# Control.net
KiCad netlist of a schematic drawn in Altium Designer
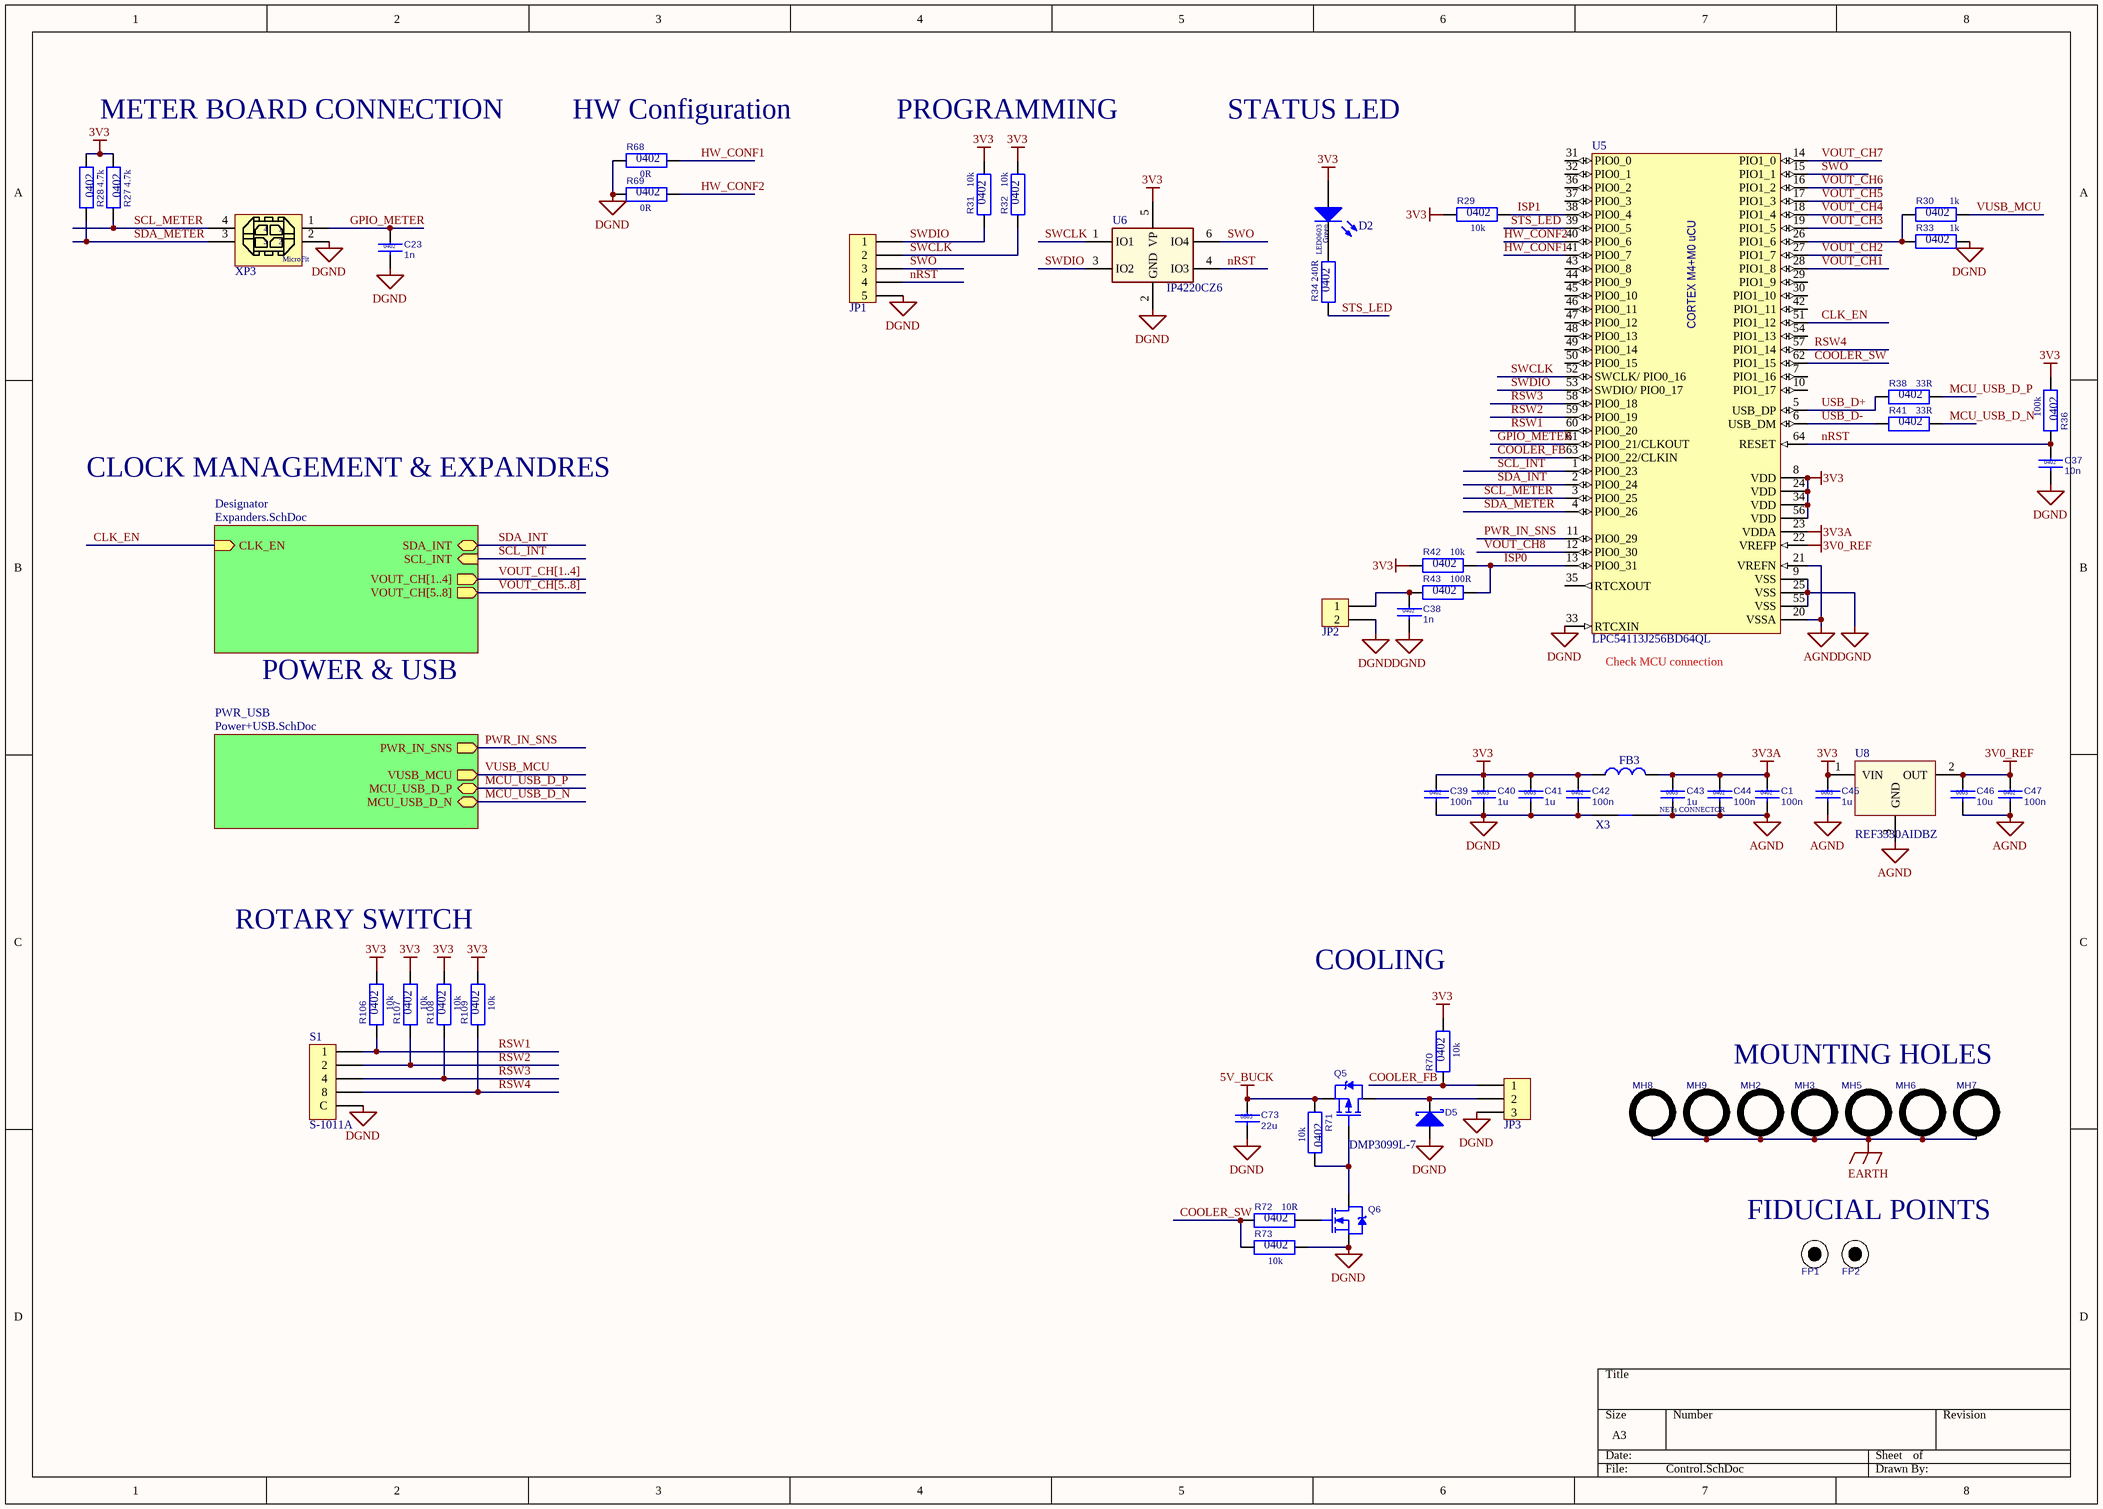
[diagram p0: Control.SchDoc]

(export (version "E")
  (design (tool "Eeschema 10.0.6"))
  (components
    (comp (ref "C1")
      (value "100n")
      (footprint "CC0402M")
      (description "Chip ceramic capacitor")
      (fields
        (field (name "CASE") "0402")
        (field (name "PARTNUMBER") "CC0402K-X7R-25V-100N-M")
        (field (name "MANUFACTURER") "Murata")
        (field (name "PUBLISHER") "alexey.savchenko")
      )
      (libsource (lib "AltiumLib") (part "Capacitor_nonpolar"))
    )
    (comp (ref "C23")
      (value "1n")
      (footprint "CC0402M")
      (description "Chip ceramic capacitor")
      (fields
        (field (name "CASE") "0402")
        (field (name "PARTNUMBER") "CC0402K-X7R-50V-1N-M")
        (field (name "MANUFACTURER") "Yageo")
        (field (name "PUBLISHER") "alexey.savchenko")
      )
      (libsource (lib "AltiumLib") (part "Capacitor_nonpolar"))
    )
    (comp (ref "C37")
      (value "10n")
      (footprint "CC0402M")
      (description "Chip ceramic capacitor")
      (fields
        (field (name "CASE") "0402")
        (field (name "PARTNUMBER") "CC0402K-X7R-50V-10N-M")
        (field (name "MANUFACTURER") "Yageo")
        (field (name "PUBLISHER") "alexey.savchenko")
      )
      (libsource (lib "AltiumLib") (part "Capacitor_nonpolar"))
    )
    (comp (ref "C38")
      (value "1n")
      (footprint "CC0402M")
      (description "Chip ceramic capacitor")
      (fields
        (field (name "CASE") "0402")
        (field (name "PARTNUMBER") "CC0402K-X7R-50V-1N-M")
        (field (name "MANUFACTURER") "Yageo")
        (field (name "PUBLISHER") "alexey.savchenko")
      )
      (libsource (lib "AltiumLib") (part "Capacitor_nonpolar"))
    )
    (comp (ref "C39")
      (value "100n")
      (footprint "CC0402M")
      (description "Chip ceramic capacitor")
      (fields
        (field (name "CASE") "0402")
        (field (name "PARTNUMBER") "CC0402K-X7R-25V-100N-M")
        (field (name "MANUFACTURER") "Murata")
        (field (name "PUBLISHER") "alexey.savchenko")
      )
      (libsource (lib "AltiumLib") (part "Capacitor_nonpolar"))
    )
    (comp (ref "C40")
      (value "1u")
      (footprint "CC0603M")
      (description "Chip ceramic capacitor")
      (fields
        (field (name "CASE") "0603")
        (field (name "PARTNUMBER") "CC0603K-X7R-10V-1U-M")
        (field (name "MANUFACTURER") "Samsung")
        (field (name "PUBLISHER") "alexey.savchenko")
      )
      (libsource (lib "AltiumLib") (part "Capacitor_nonpolar"))
    )
    (comp (ref "C41")
      (value "1u")
      (footprint "CC0603M")
      (description "Chip ceramic capacitor")
      (fields
        (field (name "CASE") "0603")
        (field (name "PARTNUMBER") "CC0603K-X7R-10V-1U-M")
        (field (name "MANUFACTURER") "Samsung")
        (field (name "PUBLISHER") "alexey.savchenko")
      )
      (libsource (lib "AltiumLib") (part "Capacitor_nonpolar"))
    )
    (comp (ref "C42")
      (value "100n")
      (footprint "CC0402M")
      (description "Chip ceramic capacitor")
      (fields
        (field (name "CASE") "0402")
        (field (name "PARTNUMBER") "CC0402K-X7R-25V-100N-M")
        (field (name "MANUFACTURER") "Murata")
        (field (name "PUBLISHER") "alexey.savchenko")
      )
      (libsource (lib "AltiumLib") (part "Capacitor_nonpolar"))
    )
    (comp (ref "C43")
      (value "1u")
      (footprint "CC0603M")
      (description "Chip ceramic capacitor")
      (fields
        (field (name "CASE") "0603")
        (field (name "PARTNUMBER") "CC0603K-X7R-10V-1U-M")
        (field (name "MANUFACTURER") "Samsung")
        (field (name "PUBLISHER") "alexey.savchenko")
      )
      (libsource (lib "AltiumLib") (part "Capacitor_nonpolar"))
    )
    (comp (ref "C44")
      (value "100n")
      (footprint "CC0402M")
      (description "Chip ceramic capacitor")
      (fields
        (field (name "CASE") "0402")
        (field (name "PARTNUMBER") "CC0402K-X7R-25V-100N-M")
        (field (name "MANUFACTURER") "Murata")
        (field (name "PUBLISHER") "alexey.savchenko")
      )
      (libsource (lib "AltiumLib") (part "Capacitor_nonpolar"))
    )
    (comp (ref "C45")
      (value "1u")
      (footprint "CC0603M")
      (description "Chip ceramic capacitor")
      (fields
        (field (name "CASE") "0603")
        (field (name "PARTNUMBER") "CC0603K-X7R-10V-1U-M")
        (field (name "MANUFACTURER") "Samsung")
        (field (name "PUBLISHER") "alexey.savchenko")
      )
      (libsource (lib "AltiumLib") (part "Capacitor_nonpolar"))
    )
    (comp (ref "C46")
      (value "10u")
      (footprint "CC0603M")
      (description "Chip ceramic capacitor")
      (fields
        (field (name "CASE") "0603")
        (field (name "PARTNUMBER") "CC0603K-X5R-10V-10U-M")
        (field (name "MANUFACTURER") "Murata")
        (field (name "PUBLISHER") "alexey.savchenko")
      )
      (libsource (lib "AltiumLib") (part "Capacitor_nonpolar"))
    )
    (comp (ref "C47")
      (value "100n")
      (footprint "CC0402M")
      (description "Chip ceramic capacitor")
      (fields
        (field (name "CASE") "0402")
        (field (name "PARTNUMBER") "CC0402K-X7R-25V-100N-M")
        (field (name "MANUFACTURER") "Murata")
        (field (name "PUBLISHER") "alexey.savchenko")
      )
      (libsource (lib "AltiumLib") (part "Capacitor_nonpolar"))
    )
    (comp (ref "C73")
      (value "22u")
      (footprint "CC0805M")
      (description "Chip ceramic capacitor")
      (fields
        (field (name "CASE") "0805")
        (field (name "PARTNUMBER") "CC0805K-X5R-10V-22U-M")
        (field (name "MANUFACTURER") "Samsung")
        (field (name "PUBLISHER") "alexey.savchenko")
      )
      (libsource (lib "AltiumLib") (part "Capacitor_nonpolar"))
    )
    (comp (ref "D2")
      (value "150060GS75000")
      (footprint "LED0603")
      (description "LED GREEN CLEAR 0603 SMD")
      (fields
        (field (name "CASE") "LED0603")
        (field (name "COLOR") "Green")
        (field (name "MANUFACTURER") "Würth Elektronik")
        (field (name "PUBLISHER") "alexey.savchenko")
      )
      (libsource (lib "AltiumLib") (part "LED"))
    )
    (comp (ref "D5")
      (value "BAT54HT1G")
      (footprint "SOD323")
      (description "DIODE SCHOTTKY 30V 200MA SOD323")
      (fields (field (name "MANUFACTURER") "ON Semiconductor") (field (name "PUBLISHER") "alexey.savchenko"))
      (libsource (lib "AltiumLib") (part "SCHOTTKY_DIODE"))
    )
    (comp (ref "FB3")
      (value "BLM18HG102SN1D")
      (footprint "FB0603M")
      (description "FERRITE BEAD 1 KOHM 0603 1LN")
      (fields (field (name "MANUFACTURER") "Murata") (field (name "PUBLISHER") "alexey.savchenko"))
      (libsource (lib "AltiumLib") (part "FerriteBead"))
    )
    (comp (ref "FP1")
      (value "FP")
      (footprint "FP")
      (description "No BOM component to short circuit 2 nets")
      (fields (field (name "MANUFACTURER") "NULL") (field (name "PUBLISHER") "alexey.savchenko"))
      (libsource (lib "AltiumLib") (part "FP"))
    )
    (comp (ref "FP2")
      (value "FP")
      (footprint "FP")
      (description "No BOM component to short circuit 2 nets")
      (fields (field (name "MANUFACTURER") "NULL") (field (name "PUBLISHER") "alexey.savchenko"))
      (libsource (lib "AltiumLib") (part "FP"))
    )
    (comp (ref "JP1")
      (value "HEADER-2.54-THR-1x5-MV")
      (footprint "HEADER-2.54-THR-1x5-MV")
      (description "Header Connector, 2.54mm pitch, Single, 5 contacts, Male, Vertical")
      (fields (field (name "MANUFACTURER") "Adam Tech") (field (name "PUBLISHER") "alexey.savchenko"))
      (libsource (lib "AltiumLib") (part "HEADER-1x5"))
    )
    (comp (ref "JP2")
      (value "HEADER-2.54-THR-1x2-MV")
      (footprint "HEADER-2.54-THR-1x2-MV")
      (description "Header Connector, 2.54mm pitch, Single, 2 contacts, Male, Vertical")
      (fields (field (name "MANUFACTURER") "Adam Tech") (field (name "PUBLISHER") "alexey.savchenko"))
      (libsource (lib "AltiumLib") (part "HEADER-1x2"))
    )
    (comp (ref "JP3")
      (value "HEADER-2.54-THR-1x3-MV")
      (footprint "HEADER-2.54-THR-1x3-MV")
      (description "Header Connector, 2.54mm pitch, Single, 3 contacts, Male, Vertical")
      (fields (field (name "MANUFACTURER") "Adam Tech") (field (name "PUBLISHER") "alexey.savchenko"))
      (libsource (lib "AltiumLib") (part "HEADER-1x3"))
    )
    (comp (ref "MH2")
      (value "MH-3.5-PLATED")
      (footprint "MH_3.5_PLATED")
      (description "Mounting Hole")
      (fields (field (name "MANUFACTURER") "NULL") (field (name "PUBLISHER") "alexey.savchenko"))
      (libsource (lib "AltiumLib") (part "MH_MISC"))
    )
    (comp (ref "MH3")
      (value "MH-3.5-PLATED")
      (footprint "MH_3.5_PLATED")
      (description "Mounting Hole")
      (fields (field (name "MANUFACTURER") "NULL") (field (name "PUBLISHER") "alexey.savchenko"))
      (libsource (lib "AltiumLib") (part "MH_MISC"))
    )
    (comp (ref "MH5")
      (value "MH-3.5-PLATED")
      (footprint "MH_3.5_PLATED")
      (description "Mounting Hole")
      (fields (field (name "MANUFACTURER") "NULL") (field (name "PUBLISHER") "alexey.savchenko"))
      (libsource (lib "AltiumLib") (part "MH_MISC"))
    )
    (comp (ref "MH6")
      (value "MH-3.5-PLATED")
      (footprint "MH_3.5_PLATED")
      (description "Mounting Hole")
      (fields (field (name "MANUFACTURER") "NULL") (field (name "PUBLISHER") "alexey.savchenko"))
      (libsource (lib "AltiumLib") (part "MH_MISC"))
    )
    (comp (ref "MH7")
      (value "MH-3.5-PLATED")
      (footprint "MH_3.5_PLATED")
      (description "Mounting Hole")
      (fields (field (name "MANUFACTURER") "NULL") (field (name "PUBLISHER") "alexey.savchenko"))
      (libsource (lib "AltiumLib") (part "MH_MISC"))
    )
    (comp (ref "MH8")
      (value "MH-3.5-PLATED")
      (footprint "MH_3.5_PLATED")
      (description "Mounting Hole")
      (fields (field (name "MANUFACTURER") "NULL") (field (name "PUBLISHER") "alexey.savchenko"))
      (libsource (lib "AltiumLib") (part "MH_MISC"))
    )
    (comp (ref "MH9")
      (value "MH-3.5-PLATED")
      (footprint "MH_3.5_PLATED")
      (description "Mounting Hole")
      (fields (field (name "MANUFACTURER") "NULL") (field (name "PUBLISHER") "alexey.savchenko"))
      (libsource (lib "AltiumLib") (part "MH_MISC"))
    )
    (comp (ref "Q5")
      (value "DMP3099L-7")
      (footprint "SOT23-3")
      (description "P-Channel 30V 3.8A (Ta) 1.08W (Ta) Surface Mount SOT-23")
      (fields (field (name "MANUFACTURER") "Diodes") (field (name "PUBLISHER") "alexey.savchenko"))
      (libsource (lib "AltiumLib") (part "MOSFET_P-CH"))
    )
    (comp (ref "Q6")
      (value "NX3020NAKW,115")
      (footprint "SOT323")
      (description "MOSFET N-CH 30V 180MA SOT323")
      (fields (field (name "MANUFACTURER") "Nexperia") (field (name "PUBLISHER") "alexey.savchenko"))
      (libsource (lib "AltiumLib") (part "MOSFET_N-CH"))
    )
    (comp (ref "R27")
      (value "4.7k")
      (footprint "RC0402M")
      (description "Chip resistor")
      (fields
        (field (name "CASE") "0402")
        (field (name "PARTNUMBER") "RC0402F-4K7-M")
        (field (name "POWER") "0.063W")
        (field (name "PUBLISHER") "alexey.savchenko")
      )
      (libsource (lib "AltiumLib") (part "Resistor"))
    )
    (comp (ref "R28")
      (value "4.7k")
      (footprint "RC0402M")
      (description "Chip resistor")
      (fields
        (field (name "CASE") "0402")
        (field (name "PARTNUMBER") "RC0402F-4K7-M")
        (field (name "POWER") "0.063W")
        (field (name "PUBLISHER") "alexey.savchenko")
      )
      (libsource (lib "AltiumLib") (part "Resistor"))
    )
    (comp (ref "R29")
      (value "10k")
      (footprint "RC0402M")
      (description "Chip resistor")
      (fields
        (field (name "CASE") "0402")
        (field (name "PARTNUMBER") "RC0402F-10K-M")
        (field (name "POWER") "0.063W")
        (field (name "PUBLISHER") "alexey.savchenko")
      )
      (libsource (lib "AltiumLib") (part "Resistor"))
    )
    (comp (ref "R30")
      (value "1k")
      (footprint "RC0402M")
      (description "Chip resistor")
      (fields
        (field (name "CASE") "0402")
        (field (name "PARTNUMBER") "RC0402F-1K-M")
        (field (name "POWER") "0.063W")
        (field (name "PUBLISHER") "alexey.savchenko")
      )
      (libsource (lib "AltiumLib") (part "Resistor"))
    )
    (comp (ref "R31")
      (value "10k")
      (footprint "RC0402M")
      (description "Chip resistor")
      (fields
        (field (name "CASE") "0402")
        (field (name "PARTNUMBER") "RC0402F-10K-M")
        (field (name "POWER") "0.063W")
        (field (name "PUBLISHER") "alexey.savchenko")
      )
      (libsource (lib "AltiumLib") (part "Resistor"))
    )
    (comp (ref "R32")
      (value "10k")
      (footprint "RC0402M")
      (description "Chip resistor")
      (fields
        (field (name "CASE") "0402")
        (field (name "PARTNUMBER") "RC0402F-10K-M")
        (field (name "POWER") "0.063W")
        (field (name "PUBLISHER") "alexey.savchenko")
      )
      (libsource (lib "AltiumLib") (part "Resistor"))
    )
    (comp (ref "R33")
      (value "1k")
      (footprint "RC0402M")
      (description "Chip resistor")
      (fields
        (field (name "CASE") "0402")
        (field (name "PARTNUMBER") "RC0402F-1K-M")
        (field (name "POWER") "0.063W")
        (field (name "PUBLISHER") "alexey.savchenko")
      )
      (libsource (lib "AltiumLib") (part "Resistor"))
    )
    (comp (ref "R34")
      (value "240R")
      (footprint "RC0402M")
      (description "Chip resistor")
      (fields
        (field (name "CASE") "0402")
        (field (name "PARTNUMBER") "RC0402F-240R-M")
        (field (name "POWER") "0.063W")
        (field (name "PUBLISHER") "alexey.savchenko")
      )
      (libsource (lib "AltiumLib") (part "Resistor"))
    )
    (comp (ref "R36")
      (value "100k")
      (footprint "RC0402M")
      (description "Chip resistor")
      (fields
        (field (name "CASE") "0402")
        (field (name "PARTNUMBER") "RC0402F-100K-M")
        (field (name "POWER") "0.063W")
        (field (name "PUBLISHER") "alexey.savchenko")
      )
      (libsource (lib "AltiumLib") (part "Resistor"))
    )
    (comp (ref "R38")
      (value "33R")
      (footprint "RC0402M")
      (description "Chip resistor")
      (fields
        (field (name "CASE") "0402")
        (field (name "PARTNUMBER") "RC0402F-33R-M")
        (field (name "POWER") "0.063W")
        (field (name "PUBLISHER") "alexey.savchenko")
      )
      (libsource (lib "AltiumLib") (part "Resistor"))
    )
    (comp (ref "R41")
      (value "33R")
      (footprint "RC0402M")
      (description "Chip resistor")
      (fields
        (field (name "CASE") "0402")
        (field (name "PARTNUMBER") "RC0402F-33R-M")
        (field (name "POWER") "0.063W")
        (field (name "PUBLISHER") "alexey.savchenko")
      )
      (libsource (lib "AltiumLib") (part "Resistor"))
    )
    (comp (ref "R42")
      (value "10k")
      (footprint "RC0402M")
      (description "Chip resistor")
      (fields
        (field (name "CASE") "0402")
        (field (name "PARTNUMBER") "RC0402F-10K-M")
        (field (name "POWER") "0.063W")
        (field (name "PUBLISHER") "alexey.savchenko")
      )
      (libsource (lib "AltiumLib") (part "Resistor"))
    )
    (comp (ref "R43")
      (value "100R")
      (footprint "RC0402M")
      (description "Chip resistor")
      (fields
        (field (name "CASE") "0402")
        (field (name "PARTNUMBER") "RC0402F-100R-M")
        (field (name "POWER") "0.063W")
        (field (name "PUBLISHER") "alexey.savchenko")
      )
      (libsource (lib "AltiumLib") (part "Resistor"))
    )
    (comp (ref "R68")
      (value "0R")
      (footprint "RC0402M")
      (description "Chip resistor")
      (fields
        (field (name "CASE") "0402")
        (field (name "PARTNUMBER") "RC0402F-0R-M")
        (field (name "MANUFACTURER") "Yageo")
        (field (name "PUBLISHER") "alexey.savchenko")
      )
      (libsource (lib "AltiumLib") (part "Resistor"))
    )
    (comp (ref "R69")
      (value "0R")
      (footprint "RC0402M")
      (description "Chip resistor")
      (fields
        (field (name "CASE") "0402")
        (field (name "PARTNUMBER") "RC0402F-0R-M")
        (field (name "MANUFACTURER") "Yageo")
        (field (name "PUBLISHER") "alexey.savchenko")
      )
      (libsource (lib "AltiumLib") (part "Resistor"))
    )
    (comp (ref "R70")
      (value "10k")
      (footprint "RC0402M")
      (description "Chip resistor")
      (fields
        (field (name "CASE") "0402")
        (field (name "PARTNUMBER") "RC0402F-10K-M")
        (field (name "MANUFACTURER") "Yageo")
        (field (name "PUBLISHER") "alexey.savchenko")
      )
      (libsource (lib "AltiumLib") (part "Resistor"))
    )
    (comp (ref "R71")
      (value "10k")
      (footprint "RC0402M")
      (description "Chip resistor")
      (fields
        (field (name "CASE") "0402")
        (field (name "PARTNUMBER") "RC0402F-10K-M")
        (field (name "MANUFACTURER") "Yageo")
        (field (name "PUBLISHER") "alexey.savchenko")
      )
      (libsource (lib "AltiumLib") (part "Resistor"))
    )
    (comp (ref "R72")
      (value "10R")
      (footprint "RC0402M")
      (description "Chip resistor")
      (fields
        (field (name "CASE") "0402")
        (field (name "PARTNUMBER") "RC0402F-10R-M")
        (field (name "MANUFACTURER") "Yageo")
        (field (name "PUBLISHER") "alexey.savchenko")
      )
      (libsource (lib "AltiumLib") (part "Resistor"))
    )
    (comp (ref "R73")
      (value "10k")
      (footprint "RC0402M")
      (description "Chip resistor")
      (fields
        (field (name "CASE") "0402")
        (field (name "PARTNUMBER") "RC0402F-10K-M")
        (field (name "MANUFACTURER") "Yageo")
        (field (name "PUBLISHER") "alexey.savchenko")
      )
      (libsource (lib "AltiumLib") (part "Resistor"))
    )
    (comp (ref "R106")
      (value "10k")
      (footprint "RC0402M")
      (description "Chip resistor")
      (fields
        (field (name "CASE") "0402")
        (field (name "PARTNUMBER") "RC0402F-10K-M")
        (field (name "MANUFACTURER") "Yageo")
        (field (name "PUBLISHER") "alexey.savchenko")
      )
      (libsource (lib "AltiumLib") (part "Resistor"))
    )
    (comp (ref "R107")
      (value "10k")
      (footprint "RC0402M")
      (description "Chip resistor")
      (fields
        (field (name "CASE") "0402")
        (field (name "PARTNUMBER") "RC0402F-10K-M")
        (field (name "MANUFACTURER") "Yageo")
        (field (name "PUBLISHER") "alexey.savchenko")
      )
      (libsource (lib "AltiumLib") (part "Resistor"))
    )
    (comp (ref "R108")
      (value "10k")
      (footprint "RC0402M")
      (description "Chip resistor")
      (fields
        (field (name "CASE") "0402")
        (field (name "PARTNUMBER") "RC0402F-10K-M")
        (field (name "MANUFACTURER") "Yageo")
        (field (name "PUBLISHER") "alexey.savchenko")
      )
      (libsource (lib "AltiumLib") (part "Resistor"))
    )
    (comp (ref "R109")
      (value "10k")
      (footprint "RC0402M")
      (description "Chip resistor")
      (fields
        (field (name "CASE") "0402")
        (field (name "PARTNUMBER") "RC0402F-10K-M")
        (field (name "MANUFACTURER") "Yageo")
        (field (name "PUBLISHER") "alexey.savchenko")
      )
      (libsource (lib "AltiumLib") (part "Resistor"))
    )
    (comp (ref "S1")
      (value "S-1011A")
      (footprint "S-1011A")
      (description "Dip Switch Hexadecimal 16 Position Through Hole, Right Angle Rotary for Tool Actuator 100mA 5VDC")
      (fields
        (field (name "MANUFACTURER") "Nidec Copal Electronics")
        (field (name "PUBLISHER") "alexey.savchenko")
      )
      (libsource (lib "AltiumLib") (part "S-1011A"))
    )
    (comp (ref "U5")
      (value "LPC54113J256BD64QL")
      (footprint "LQFP-64")
      (description "IC MCU 32BIT 256KB FLASH 64LQFP")
      (fields (field (name "MANUFACTURER") "NXP") (field (name "PUBLISHER") "alexey.savchenko"))
      (libsource (lib "AltiumLib") (part "LPC54113J256BD64QL"))
    )
    (comp (ref "U6")
      (value "IP4220CZ6")
      (footprint "TSOP-6")
      (description "TVS DIODE 5.5V 6TSOP")
      (fields (field (name "MANUFACTURER") "Nexperia") (field (name "PUBLISHER") "alexey.savchenko"))
      (libsource (lib "AltiumLib") (part "IP4220CZ6"))
    )
    (comp (ref "U8")
      (value "REF3330AIDBZ")
      (footprint "SOT23-3")
      (description "IC VREF SERIES 0.15% SOT23-3")
      (fields (field (name "MANUFACTURER") "TI") (field (name "PUBLISHER") "alexey.savchenko"))
      (libsource (lib "AltiumLib") (part "REF3330AIDBZ"))
    )
    (comp (ref "X3")
      (value "NETs_CONNECTOR")
      (footprint "NETs_CONNECTOR")
      (description "No BOM component to short circuit 2 nets")
      (fields (field (name "MANUFACTURER") "NULL") (field (name "PUBLISHER") "alexey.savchenko"))
      (libsource (lib "AltiumLib") (part "NETs_CONNECTOR"))
    )
    (comp (ref "XP3")
      (value "0447690401")
      (footprint "0447690401")
      (fields (field (name "MANUFACTURER") "Molex") (field (name "PUBLISHER") "alexey.savchenko"))
      (libsource (lib "AltiumLib") (part "MicroFit-2x2"))
    )
  )
  (nets
    (net (code "1") (name "/CLK_EN") (class "Default")
      (node (ref "U5") (pin "51") (pinfunction "PIO1_12_51") (pintype "bidirectional"))
    )
    (net (code "2") (name "/COOLER_FB") (class "Default")
      (node (ref "JP3") (pin "1") (pinfunction "1_1") (pintype "passive"))
      (node (ref "R70") (pin "1") (pinfunction "1_1") (pintype "passive"))
      (node (ref "U5") (pin "63") (pinfunction "PIO0_22/CLKIN_63") (pintype "bidirectional"))
    )
    (net (code "3") (name "/COOLER_SW") (class "Default")
      (node (ref "R72") (pin "1") (pinfunction "1_1") (pintype "passive"))
      (node (ref "R73") (pin "1") (pinfunction "1_1") (pintype "passive"))
      (node (ref "U5") (pin "62") (pinfunction "PIO1_15_62") (pintype "bidirectional"))
    )
    (net (code "4") (name "/GPIO_METER") (class "Default")
      (node (ref "C23") (pin "1") (pinfunction "1_1") (pintype "passive"))
      (node (ref "U5") (pin "61") (pinfunction "PIO0_21/CLKOUT_61") (pintype "bidirectional"))
      (node (ref "XP3") (pin "1") (pinfunction "1_1") (pintype "passive"))
    )
    (net (code "5") (name "/HW_CONF1") (class "Default")
      (node (ref "R68") (pin "2") (pinfunction "2_2") (pintype "passive"))
      (node (ref "U5") (pin "41") (pinfunction "PIO0_7_41") (pintype "bidirectional"))
    )
    (net (code "6") (name "/HW_CONF2") (class "Default")
      (node (ref "R69") (pin "2") (pinfunction "2_2") (pintype "passive"))
      (node (ref "U5") (pin "40") (pinfunction "PIO0_6_40") (pintype "bidirectional"))
    )
    (net (code "7") (name "/ISP0") (class "Default")
      (node (ref "R42") (pin "2") (pinfunction "2_2") (pintype "passive"))
      (node (ref "R43") (pin "2") (pinfunction "2_2") (pintype "passive"))
      (node (ref "U5") (pin "13") (pinfunction "PIO0_31_13") (pintype "bidirectional"))
    )
    (net (code "8") (name "/ISP1") (class "Default")
      (node (ref "R29") (pin "2") (pinfunction "2_2") (pintype "passive"))
      (node (ref "U5") (pin "38") (pinfunction "PIO0_4_38") (pintype "bidirectional"))
    )
    (net (code "9") (name "/MCU_USB_D_N") (class "Default")
      (node (ref "R41") (pin "2") (pinfunction "2_2") (pintype "passive"))
    )
    (net (code "10") (name "/MCU_USB_D_P") (class "Default")
      (node (ref "R38") (pin "2") (pinfunction "2_2") (pintype "passive"))
    )
    (net (code "11") (name "/PWR_IN_SNS") (class "Default")
      (node (ref "U5") (pin "11") (pinfunction "PIO0_29_11") (pintype "bidirectional"))
    )
    (net (code "12") (name "/RSW1") (class "Default")
      (node (ref "R106") (pin "1") (pinfunction "1_1") (pintype "passive"))
      (node (ref "S1") (pin "1") (pinfunction "1_1") (pintype "passive"))
      (node (ref "U5") (pin "60") (pinfunction "PIO0_20_60") (pintype "bidirectional"))
    )
    (net (code "13") (name "/RSW2") (class "Default")
      (node (ref "R107") (pin "1") (pinfunction "1_1") (pintype "passive"))
      (node (ref "S1") (pin "2") (pinfunction "2_2") (pintype "passive"))
      (node (ref "U5") (pin "59") (pinfunction "PIO0_19_59") (pintype "bidirectional"))
    )
    (net (code "14") (name "/RSW3") (class "Default")
      (node (ref "R108") (pin "1") (pinfunction "1_1") (pintype "passive"))
      (node (ref "S1") (pin "4") (pinfunction "4_4") (pintype "passive"))
      (node (ref "U5") (pin "58") (pinfunction "PIO0_18_58") (pintype "bidirectional"))
    )
    (net (code "15") (name "/RSW4") (class "Default")
      (node (ref "R109") (pin "1") (pinfunction "1_1") (pintype "passive"))
      (node (ref "S1") (pin "8") (pinfunction "8_8") (pintype "passive"))
      (node (ref "U5") (pin "57") (pinfunction "PIO1_14_57") (pintype "bidirectional"))
    )
    (net (code "16") (name "/SCL_INT") (class "Default")
      (node (ref "U5") (pin "1") (pinfunction "PIO0_23_1") (pintype "bidirectional"))
    )
    (net (code "17") (name "/SCL_METER") (class "Default")
      (node (ref "R27") (pin "1") (pinfunction "1_1") (pintype "passive"))
      (node (ref "U5") (pin "3") (pinfunction "PIO0_25_3") (pintype "bidirectional"))
      (node (ref "XP3") (pin "4") (pinfunction "4_4") (pintype "passive"))
    )
    (net (code "18") (name "/SDA_INT") (class "Default")
      (node (ref "U5") (pin "2") (pinfunction "PIO0_24_2") (pintype "bidirectional"))
    )
    (net (code "19") (name "/SDA_METER") (class "Default")
      (node (ref "R28") (pin "1") (pinfunction "1_1") (pintype "passive"))
      (node (ref "U5") (pin "4") (pinfunction "PIO0_26_4") (pintype "bidirectional"))
      (node (ref "XP3") (pin "3") (pinfunction "3_3") (pintype "passive"))
    )
    (net (code "20") (name "/STS_LED") (class "Default")
      (node (ref "R34") (pin "1") (pinfunction "1_1") (pintype "passive"))
      (node (ref "U5") (pin "39") (pinfunction "PIO0_5_39") (pintype "bidirectional"))
    )
    (net (code "21") (name "/SWCLK") (class "Default")
      (node (ref "JP1") (pin "2") (pinfunction "2_2") (pintype "passive"))
      (node (ref "R32") (pin "1") (pinfunction "1_1") (pintype "passive"))
      (node (ref "U5") (pin "52") (pinfunction "SWCLK/_PIO0_16_52") (pintype "bidirectional"))
      (node (ref "U6") (pin "1") (pinfunction "IO1_1") (pintype "passive"))
    )
    (net (code "22") (name "/SWDIO") (class "Default")
      (node (ref "JP1") (pin "1") (pinfunction "1_1") (pintype "passive"))
      (node (ref "R31") (pin "1") (pinfunction "1_1") (pintype "passive"))
      (node (ref "U5") (pin "53") (pinfunction "SWDIO/_PIO0_17_53") (pintype "bidirectional"))
      (node (ref "U6") (pin "3") (pinfunction "IO2_3") (pintype "passive"))
    )
    (net (code "23") (name "/SWO") (class "Default")
      (node (ref "JP1") (pin "3") (pinfunction "3_3") (pintype "passive"))
      (node (ref "U5") (pin "15") (pinfunction "PIO1_1_15") (pintype "bidirectional"))
      (node (ref "U6") (pin "6") (pinfunction "IO4_6") (pintype "passive"))
    )
    (net (code "24") (name "/USB_D+") (class "Default")
      (node (ref "R38") (pin "1") (pinfunction "1_1") (pintype "passive"))
      (node (ref "U5") (pin "5") (pinfunction "USB_DP_5") (pintype "bidirectional"))
    )
    (net (code "25") (name "/USB_D-") (class "Default")
      (node (ref "R41") (pin "1") (pinfunction "1_1") (pintype "passive"))
      (node (ref "U5") (pin "6") (pinfunction "USB_DM_6") (pintype "bidirectional"))
    )
    (net (code "26") (name "/VOUT_CH1") (class "Default")
      (node (ref "U5") (pin "28") (pinfunction "PIO1_8_28") (pintype "bidirectional"))
    )
    (net (code "27") (name "/VOUT_CH2") (class "Default")
      (node (ref "U5") (pin "27") (pinfunction "PIO1_7_27") (pintype "bidirectional"))
    )
    (net (code "28") (name "/VOUT_CH3") (class "Default")
      (node (ref "U5") (pin "19") (pinfunction "PIO1_5_19") (pintype "bidirectional"))
    )
    (net (code "29") (name "/VOUT_CH4") (class "Default")
      (node (ref "U5") (pin "18") (pinfunction "PIO1_4_18") (pintype "bidirectional"))
    )
    (net (code "30") (name "/VOUT_CH5") (class "Default")
      (node (ref "U5") (pin "17") (pinfunction "PIO1_3_17") (pintype "bidirectional"))
    )
    (net (code "31") (name "/VOUT_CH6") (class "Default")
      (node (ref "U5") (pin "16") (pinfunction "PIO1_2_16") (pintype "bidirectional"))
    )
    (net (code "32") (name "/VOUT_CH7") (class "Default")
      (node (ref "U5") (pin "14") (pinfunction "PIO1_0_14") (pintype "bidirectional"))
    )
    (net (code "33") (name "/VOUT_CH8") (class "Default")
      (node (ref "U5") (pin "12") (pinfunction "PIO0_30_12") (pintype "bidirectional"))
    )
    (net (code "36") (name "/VUSB_MCU") (class "Default")
      (node (ref "R30") (pin "2") (pinfunction "2_2") (pintype "passive"))
    )
    (net (code "37") (name "/nRST") (class "Default")
      (node (ref "C37") (pin "1") (pinfunction "1_1") (pintype "passive"))
      (node (ref "JP1") (pin "4") (pinfunction "4_4") (pintype "passive"))
      (node (ref "R36") (pin "1") (pinfunction "1_1") (pintype "passive"))
      (node (ref "U5") (pin "64") (pinfunction "RESET_64") (pintype "input"))
      (node (ref "U6") (pin "4") (pinfunction "IO3_4") (pintype "passive"))
    )
    (net (code "38") (name "3V0_REF") (class "Default")
      (node (ref "C46") (pin "1") (pinfunction "1_1") (pintype "passive"))
      (node (ref "C47") (pin "1") (pinfunction "1_1") (pintype "passive"))
      (node (ref "U5") (pin "22") (pinfunction "VREFP_22") (pintype "input"))
      (node (ref "U8") (pin "2") (pinfunction "OUT_2") (pintype "passive"))
    )
    (net (code "39") (name "3V3") (class "Default")
      (node (ref "C39") (pin "1") (pinfunction "1_1") (pintype "passive"))
      (node (ref "C40") (pin "1") (pinfunction "1_1") (pintype "passive"))
      (node (ref "C41") (pin "1") (pinfunction "1_1") (pintype "passive"))
      (node (ref "C42") (pin "1") (pinfunction "1_1") (pintype "passive"))
      (node (ref "C45") (pin "1") (pinfunction "1_1") (pintype "passive"))
      (node (ref "D2") (pin "2") (pinfunction "A_2") (pintype "passive"))
      (node (ref "FB3") (pin "1") (pinfunction "1_1") (pintype "passive"))
      (node (ref "R106") (pin "2") (pinfunction "2_2") (pintype "passive"))
      (node (ref "R107") (pin "2") (pinfunction "2_2") (pintype "passive"))
      (node (ref "R108") (pin "2") (pinfunction "2_2") (pintype "passive"))
      (node (ref "R109") (pin "2") (pinfunction "2_2") (pintype "passive"))
      (node (ref "R27") (pin "2") (pinfunction "2_2") (pintype "passive"))
      (node (ref "R28") (pin "2") (pinfunction "2_2") (pintype "passive"))
      (node (ref "R29") (pin "1") (pinfunction "1_1") (pintype "passive"))
      (node (ref "R31") (pin "2") (pinfunction "2_2") (pintype "passive"))
      (node (ref "R32") (pin "2") (pinfunction "2_2") (pintype "passive"))
      (node (ref "R36") (pin "2") (pinfunction "2_2") (pintype "passive"))
      (node (ref "R42") (pin "1") (pinfunction "1_1") (pintype "passive"))
      (node (ref "R70") (pin "2") (pinfunction "2_2") (pintype "passive"))
      (node (ref "U5") (pin "24") (pinfunction "VDD_24") (pintype "power_in"))
      (node (ref "U5") (pin "34") (pinfunction "VDD_34") (pintype "power_in"))
      (node (ref "U5") (pin "56") (pinfunction "VDD_56") (pintype "power_in"))
      (node (ref "U5") (pin "8") (pinfunction "VDD_8") (pintype "power_in"))
      (node (ref "U6") (pin "5") (pinfunction "VP_5") (pintype "passive"))
      (node (ref "U8") (pin "1") (pinfunction "VIN_1") (pintype "passive"))
    )
    (net (code "40") (name "3V3A") (class "Default")
      (node (ref "C1") (pin "1") (pinfunction "1_1") (pintype "passive"))
      (node (ref "C43") (pin "1") (pinfunction "1_1") (pintype "passive"))
      (node (ref "C44") (pin "1") (pinfunction "1_1") (pintype "passive"))
      (node (ref "FB3") (pin "2") (pinfunction "2_2") (pintype "passive"))
      (node (ref "U5") (pin "23") (pinfunction "VDDA_23") (pintype "power_in"))
    )
    (net (code "41") (name "5V_BUCK") (class "Default")
      (node (ref "C73") (pin "1") (pinfunction "1_1") (pintype "passive"))
      (node (ref "Q5") (pin "2") (pinfunction "S_2") (pintype "passive"))
      (node (ref "R71") (pin "1") (pinfunction "1_1") (pintype "passive"))
    )
    (net (code "42") (name "AGND") (class "Default")
      (node (ref "C1") (pin "2") (pinfunction "2_2") (pintype "passive"))
      (node (ref "C43") (pin "2") (pinfunction "2_2") (pintype "passive"))
      (node (ref "C44") (pin "2") (pinfunction "2_2") (pintype "passive"))
      (node (ref "C45") (pin "2") (pinfunction "2_2") (pintype "passive"))
      (node (ref "C46") (pin "2") (pinfunction "2_2") (pintype "passive"))
      (node (ref "C47") (pin "2") (pinfunction "2_2") (pintype "passive"))
      (node (ref "U5") (pin "20") (pinfunction "VSSA_20") (pintype "power_in"))
      (node (ref "U5") (pin "21") (pinfunction "VREFN_21") (pintype "input"))
      (node (ref "U8") (pin "3") (pinfunction "GND_3") (pintype "passive"))
      (node (ref "X3") (pin "1") (pinfunction "1_1") (pintype "passive"))
    )
    (net (code "43") (name "DGND") (class "Default")
      (node (ref "C23") (pin "2") (pinfunction "2_2") (pintype "passive"))
      (node (ref "C37") (pin "2") (pinfunction "2_2") (pintype "passive"))
      (node (ref "C38") (pin "2") (pinfunction "2_2") (pintype "passive"))
      (node (ref "C39") (pin "2") (pinfunction "2_2") (pintype "passive"))
      (node (ref "C40") (pin "2") (pinfunction "2_2") (pintype "passive"))
      (node (ref "C41") (pin "2") (pinfunction "2_2") (pintype "passive"))
      (node (ref "C42") (pin "2") (pinfunction "2_2") (pintype "passive"))
      (node (ref "C73") (pin "2") (pinfunction "2_2") (pintype "passive"))
      (node (ref "D5") (pin "2") (pinfunction "A_2") (pintype "passive"))
      (node (ref "JP1") (pin "5") (pinfunction "5_5") (pintype "passive"))
      (node (ref "JP2") (pin "2") (pinfunction "2_2") (pintype "passive"))
      (node (ref "JP3") (pin "3") (pinfunction "3_3") (pintype "passive"))
      (node (ref "Q6") (pin "2") (pinfunction "S_2") (pintype "passive"))
      (node (ref "R33") (pin "2") (pinfunction "2_2") (pintype "passive"))
      (node (ref "R68") (pin "1") (pinfunction "1_1") (pintype "passive"))
      (node (ref "R69") (pin "1") (pinfunction "1_1") (pintype "passive"))
      (node (ref "R73") (pin "2") (pinfunction "2_2") (pintype "passive"))
      (node (ref "S1") (pin "C") (pinfunction "C_C") (pintype "passive"))
      (node (ref "U5") (pin "25") (pinfunction "VSS_25") (pintype "power_in"))
      (node (ref "U5") (pin "33") (pinfunction "RTCXIN_33") (pintype "input"))
      (node (ref "U5") (pin "55") (pinfunction "VSS_55") (pintype "power_in"))
      (node (ref "U5") (pin "9") (pinfunction "VSS_9") (pintype "power_in"))
      (node (ref "U6") (pin "2") (pinfunction "GND_2") (pintype "passive"))
      (node (ref "X3") (pin "2") (pinfunction "2_2") (pintype "passive"))
      (node (ref "XP3") (pin "2") (pinfunction "2_2") (pintype "passive"))
    )
    (net (code "44") (name "EARTH") (class "Default")
      (node (ref "MH2") (pin "0") (pinfunction "0_0") (pintype "passive"))
      (node (ref "MH3") (pin "0") (pinfunction "0_0") (pintype "passive"))
      (node (ref "MH5") (pin "0") (pinfunction "0_0") (pintype "passive"))
      (node (ref "MH6") (pin "0") (pinfunction "0_0") (pintype "passive"))
      (node (ref "MH7") (pin "0") (pinfunction "0_0") (pintype "passive"))
      (node (ref "MH8") (pin "0") (pinfunction "0_0") (pintype "passive"))
      (node (ref "MH9") (pin "0") (pinfunction "0_0") (pintype "passive"))
    )
    (net (code "45") (name "Net-(C38-Pad1)") (class "Default")
      (node (ref "C38") (pin "1") (pinfunction "1_1") (pintype "passive"))
      (node (ref "JP2") (pin "1") (pinfunction "1_1") (pintype "passive"))
      (node (ref "R43") (pin "1") (pinfunction "1_1") (pintype "passive"))
    )
    (net (code "46") (name "Net-(D2-K)") (class "Default")
      (node (ref "D2") (pin "1") (pinfunction "K_1") (pintype "passive"))
      (node (ref "R34") (pin "2") (pinfunction "2_2") (pintype "passive"))
    )
    (net (code "47") (name "Net-(D5-K)") (class "Default")
      (node (ref "D5") (pin "1") (pinfunction "K_1") (pintype "passive"))
      (node (ref "JP3") (pin "2") (pinfunction "2_2") (pintype "passive"))
      (node (ref "Q5") (pin "3") (pinfunction "D_3") (pintype "passive"))
    )
    (net (code "48") (name "Net-(Q5-G)") (class "Default")
      (node (ref "Q5") (pin "1") (pinfunction "G_1") (pintype "passive"))
      (node (ref "Q6") (pin "3") (pinfunction "D_3") (pintype "passive"))
      (node (ref "R71") (pin "2") (pinfunction "2_2") (pintype "passive"))
    )
    (net (code "49") (name "Net-(Q6-G)") (class "Default")
      (node (ref "Q6") (pin "1") (pinfunction "G_1") (pintype "passive"))
      (node (ref "R72") (pin "2") (pinfunction "2_2") (pintype "passive"))
    )
    (net (code "50") (name "Net-(U5-PIO1_6)") (class "Default")
      (node (ref "R30") (pin "1") (pinfunction "1_1") (pintype "passive"))
      (node (ref "R33") (pin "1") (pinfunction "1_1") (pintype "passive"))
      (node (ref "U5") (pin "26") (pinfunction "PIO1_6_26") (pintype "bidirectional"))
    )
    (net (code "51") (name "unconnected-(U5-PIO0_0-Pad31)") (class "Default")
      (node (ref "U5") (pin "31") (pinfunction "PIO0_0_31") (pintype "bidirectional"))
    )
    (net (code "52") (name "unconnected-(U5-PIO0_1-Pad32)") (class "Default")
      (node (ref "U5") (pin "32") (pinfunction "PIO0_1_32") (pintype "bidirectional"))
    )
    (net (code "53") (name "unconnected-(U5-PIO0_2-Pad36)") (class "Default")
      (node (ref "U5") (pin "36") (pinfunction "PIO0_2_36") (pintype "bidirectional"))
    )
    (net (code "54") (name "unconnected-(U5-PIO0_3-Pad37)") (class "Default")
      (node (ref "U5") (pin "37") (pinfunction "PIO0_3_37") (pintype "bidirectional"))
    )
    (net (code "55") (name "unconnected-(U5-PIO0_8-Pad43)") (class "Default")
      (node (ref "U5") (pin "43") (pinfunction "PIO0_8_43") (pintype "bidirectional"))
    )
    (net (code "56") (name "unconnected-(U5-PIO0_9-Pad44)") (class "Default")
      (node (ref "U5") (pin "44") (pinfunction "PIO0_9_44") (pintype "bidirectional"))
    )
    (net (code "57") (name "unconnected-(U5-PIO0_10-Pad45)") (class "Default")
      (node (ref "U5") (pin "45") (pinfunction "PIO0_10_45") (pintype "bidirectional"))
    )
    (net (code "58") (name "unconnected-(U5-PIO0_11-Pad46)") (class "Default")
      (node (ref "U5") (pin "46") (pinfunction "PIO0_11_46") (pintype "bidirectional"))
    )
    (net (code "59") (name "unconnected-(U5-PIO0_12-Pad47)") (class "Default")
      (node (ref "U5") (pin "47") (pinfunction "PIO0_12_47") (pintype "bidirectional"))
    )
    (net (code "60") (name "unconnected-(U5-PIO0_13-Pad48)") (class "Default")
      (node (ref "U5") (pin "48") (pinfunction "PIO0_13_48") (pintype "bidirectional"))
    )
    (net (code "61") (name "unconnected-(U5-PIO0_14-Pad49)") (class "Default")
      (node (ref "U5") (pin "49") (pinfunction "PIO0_14_49") (pintype "bidirectional"))
    )
    (net (code "62") (name "unconnected-(U5-PIO0_15-Pad50)") (class "Default")
      (node (ref "U5") (pin "50") (pinfunction "PIO0_15_50") (pintype "bidirectional"))
    )
    (net (code "63") (name "unconnected-(U5-PIO1_9-Pad29)") (class "Default")
      (node (ref "U5") (pin "29") (pinfunction "PIO1_9_29") (pintype "bidirectional"))
    )
    (net (code "64") (name "unconnected-(U5-PIO1_10-Pad30)") (class "Default")
      (node (ref "U5") (pin "30") (pinfunction "PIO1_10_30") (pintype "bidirectional"))
    )
    (net (code "65") (name "unconnected-(U5-PIO1_11-Pad42)") (class "Default")
      (node (ref "U5") (pin "42") (pinfunction "PIO1_11_42") (pintype "bidirectional"))
    )
    (net (code "66") (name "unconnected-(U5-PIO1_13-Pad54)") (class "Default")
      (node (ref "U5") (pin "54") (pinfunction "PIO1_13_54") (pintype "bidirectional"))
    )
    (net (code "67") (name "unconnected-(U5-PIO1_16-Pad7)") (class "Default")
      (node (ref "U5") (pin "7") (pinfunction "PIO1_16_7") (pintype "bidirectional"))
    )
    (net (code "68") (name "unconnected-(U5-PIO1_17-Pad10)") (class "Default")
      (node (ref "U5") (pin "10") (pinfunction "PIO1_17_10") (pintype "bidirectional"))
    )
    (net (code "69") (name "unconnected-(U5-RTCXOUT-Pad35)") (class "Default")
      (node (ref "U5") (pin "35") (pinfunction "RTCXOUT_35") (pintype "output"))
    )
  )
)
